# Driver.net
KiCad netlist of a schematic drawn in Altium Designer
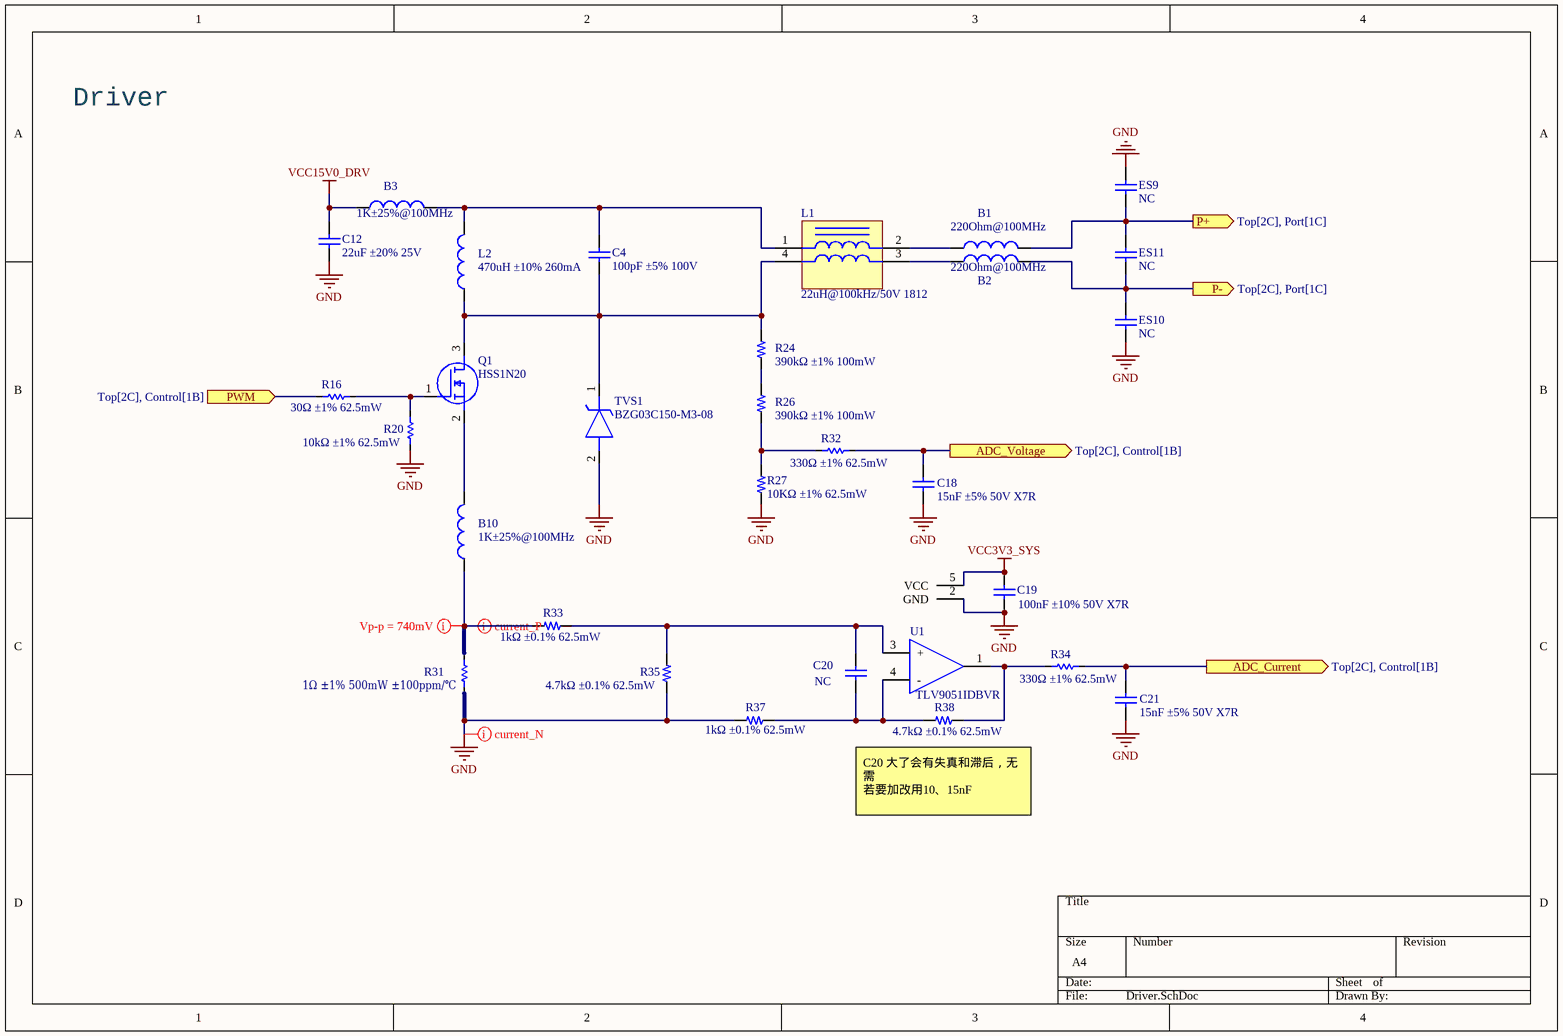
[diagram p0: Driver.SchDoc]

(export (version "E")
  (design (tool "Eeschema 10.0.6"))
  (components
    (comp (ref "B1")
      (value "220Ohm@100MHz")
      (footprint "0402-B")
      (description "BLM15AG221SN1D")
      (fields (field (name "PUBLISHER") "Altium Limited"))
      (libsource (lib "Miscellaneous Devices") (part "Inductor"))
    )
    (comp (ref "B2")
      (value "220Ohm@100MHz")
      (footprint "0402-B")
      (description "BLM15AG221SN1D")
      (fields (field (name "PUBLISHER") "Altium Limited"))
      (libsource (lib "Miscellaneous Devices") (part "Inductor"))
    )
    (comp (ref "B3")
      (value "1K±25%@100MHz")
      (footprint "0805-B")
      (description "BLM21AG102SN1D")
      (fields (field (name "PUBLISHER") "Altium Limited"))
      (libsource (lib "Miscellaneous Devices") (part "Inductor"))
    )
    (comp (ref "B10")
      (value "1K±25%@100MHz")
      (footprint "0805-B")
      (description "BLM21AG102SN1D")
      (fields (field (name "PUBLISHER") "Altium Limited"))
      (libsource (lib "Miscellaneous Devices") (part "Inductor"))
    )
    (comp (ref "C4")
      (value "100pF ±5% 100V")
      (footprint "C0603")
      (description "GCM1885C2A101JA16D")
      (fields (field (name "PUBLISHER") "Altium Limited"))
      (libsource (lib "Miscellaneous Devices") (part "Cap Semi"))
    )
    (comp (ref "C12")
      (value "22uF ±20% 25V")
      (footprint "C0805")
      (description "CL21A226MAQNNNE")
      (fields (field (name "PUBLISHER") "Altium Limited"))
      (libsource (lib "Component") (part "C0805"))
    )
    (comp (ref "C18")
      (value "15nF ±5% 50V X7R")
      (footprint "C0402")
      (description "CC0402KRX7R9BB153")
      (fields (field (name "PUBLISHER") "Altium Limited"))
      (libsource (lib "Component") (part "Cap"))
    )
    (comp (ref "C19")
      (value "100nF ±10% 50V X7R")
      (footprint "C0402")
      (description "CL05B104KO5NNNC")
      (fields (field (name "PUBLISHER") "Altium Limited"))
      (libsource (lib "Component") (part "Cap"))
    )
    (comp (ref "C20")
      (value "NC")
      (footprint "C0402")
      (description "10nF 50V 0402")
      (libsource (lib "电容") (part "100nF_1"))
    )
    (comp (ref "C21")
      (value "15nF ±5% 50V X7R")
      (footprint "C0402")
      (description "CC0402KRX7R9BB153")
      (fields (field (name "PUBLISHER") "Altium Limited"))
      (libsource (lib "Component") (part "Cap"))
    )
    (comp (ref "ES9")
      (value "NC")
      (footprint "C0402")
      (description "Capacitor (Semiconductor SIM Model)")
      (fields (field (name "PUBLISHER") "Altium Limited"))
      (libsource (lib "Miscellaneous Devices") (part "Cap Semi"))
    )
    (comp (ref "ES10")
      (value "NC")
      (footprint "C0402")
      (description "Capacitor (Semiconductor SIM Model)")
      (fields (field (name "PUBLISHER") "Altium Limited"))
      (libsource (lib "Miscellaneous Devices") (part "Cap Semi"))
    )
    (comp (ref "ES11")
      (value "NC")
      (footprint "C0402")
      (description "Capacitor (Semiconductor SIM Model)")
      (fields (field (name "PUBLISHER") "Altium Limited"))
      (libsource (lib "Miscellaneous Devices") (part "Cap Semi"))
    )
    (comp (ref "L1")
      (value "22uH@100kHz/50V 1812")
      (footprint "LINEFILTER")
      (description "APWB4532-220T2")
      (libsource (lib "Atomizer_medical") (part "Inductor_common"))
    )
    (comp (ref "L2")
      (value "470uH ±10% 260mA")
      (footprint "SP0502")
      (description "SDR0603-471KL")
      (fields (field (name "PUBLISHER") "Altium Limited"))
      (libsource (lib "Miscellaneous Devices") (part "Inductor"))
    )
    (comp (ref "Q1")
      (value "HSS1N20")
      (footprint "SamacSys:SOT95P237X122-3N")
      (description "MOSFET (N-Channel)")
      (fields
        (field (name "MANUFACTURER_PART_NUMBER") "FDN86246")
        (field (name "MOUSER PART NUMBER") "512-FDN86246")
      )
      (libsource (lib "*") (part "FDN86246"))
    )
    (comp (ref "R16")
      (value "30Ω ±1% 62.5mW")
      (footprint "R0402")
      (description "RC0402FR-0730RL")
      (fields (field (name "PUBLISHER") "Altium Limited"))
      (libsource (lib "Component") (part "R0402"))
    )
    (comp (ref "R20")
      (value "10kΩ ±1% 62.5mW")
      (footprint "R0402")
      (description "0402WGF1002TCE")
      (fields (field (name "PUBLISHER") "Altium Limited"))
      (libsource (lib "Component") (part "R0402"))
    )
    (comp (ref "R24")
      (value "390kΩ ±1% 100mW")
      (footprint "R0603")
      (description "RC0603FR-07390KL")
      (libsource (lib "Device") (part "R-0603"))
    )
    (comp (ref "R26")
      (value "390kΩ ±1% 100mW")
      (footprint "R0603")
      (description "RC0603FR-07390KL")
      (libsource (lib "Device") (part "R-0603"))
    )
    (comp (ref "R27")
      (value "10KΩ ±1% 62.5mW")
      (footprint "R0402")
      (description "0402WGF1002TCE")
      (libsource (lib "Device") (part "R-0603"))
    )
    (comp (ref "R31")
      (value "1Ω ±1% 500mW ±100ppm/℃")
      (footprint "R1206")
      (description "HP06W2F100KT5E")
      (fields (field (name "PUBLISHER") "Altium Limited"))
      (libsource (lib "Component") (part "R1206"))
    )
    (comp (ref "R32")
      (value "330Ω ±1% 62.5mW")
      (footprint "R0402")
      (description "0402WGF3300TCE")
      (fields (field (name "PUBLISHER") "Altium Limited"))
      (libsource (lib "Component") (part "R0402"))
    )
    (comp (ref "R33")
      (value "1kΩ ±0.1% 62.5mW")
      (footprint "R0402")
      (description "RT0402BRD071KL")
      (libsource (lib "Device") (part "R-0603"))
    )
    (comp (ref "R34")
      (value "330Ω ±1% 62.5mW")
      (footprint "R0402")
      (description "0402WGF3300TCE")
      (fields (field (name "PUBLISHER") "Altium Limited"))
      (libsource (lib "Component") (part "R0402"))
    )
    (comp (ref "R35")
      (value "4.7kΩ ±0.1% 62.5mW")
      (footprint "R0402")
      (description "RT0402BRD074K7L")
      (libsource (lib "Device") (part "R-0603"))
    )
    (comp (ref "R37")
      (value "1kΩ ±0.1% 62.5mW")
      (footprint "R0402")
      (description "RT0402BRD071KL")
      (libsource (lib "Device") (part "R-0603"))
    )
    (comp (ref "R38")
      (value "4.7kΩ ±0.1% 62.5mW")
      (footprint "R0402")
      (description "RT0402BRD074K7L")
      (libsource (lib "Device") (part "R-0603"))
    )
    (comp (ref "TVS1")
      (value "BZG03C150-M3-08")
      (footprint "SamacSys:DIOM5226X230N")
      (description "Zener Diode\r\nBZG03C150-M3-08")
      (fields (field (name "MOUSER PART NUMBER") "78-BZG03C150-M3-08"))
      (libsource (lib "*") (part "BZG03C150-M3-08"))
    )
    (comp (ref "U1")
      (value "TLV9051IDBVR")
      (footprint "SOT23-5")
      (description "TLV9051 适用于成本优化型应用的单路、5.5V、5MHz、15V/μs 压摆率、RRIO 运算放大器")
      (libsource (lib "IC") (part "TLV333IDBVR"))
    )
  )
  (nets
    (net (code "1") (name "/ADC_Current") (class "Default")
      (node (ref "C21") (pin "1") (pinfunction "1_1") (pintype "passive"))
      (node (ref "R34") (pin "2") (pinfunction "2_2") (pintype "passive"))
    )
    (net (code "2") (name "/ADC_Voltage") (class "Default")
      (node (ref "C18") (pin "1") (pinfunction "1_1") (pintype "passive"))
      (node (ref "R32") (pin "2") (pinfunction "2_2") (pintype "passive"))
    )
    (net (code "3") (name "/P+") (class "Default")
      (node (ref "B1") (pin "2") (pinfunction "2_2") (pintype "passive"))
      (node (ref "ES11") (pin "1") (pinfunction "1_1") (pintype "passive"))
      (node (ref "ES9") (pin "2") (pinfunction "2_2") (pintype "passive"))
    )
    (net (code "4") (name "/P-") (class "Default")
      (node (ref "B2") (pin "2") (pinfunction "2_2") (pintype "passive"))
      (node (ref "ES10") (pin "1") (pinfunction "1_1") (pintype "passive"))
      (node (ref "ES11") (pin "2") (pinfunction "2_2") (pintype "passive"))
    )
    (net (code "5") (name "/PWM") (class "Default")
      (node (ref "R16") (pin "1") (pinfunction "1_1") (pintype "passive"))
    )
    (net (code "6") (name "GND") (class "Default")
      (node (ref "C12") (pin "1") (pinfunction "1_1") (pintype "passive"))
      (node (ref "C18") (pin "2") (pinfunction "2_2") (pintype "passive"))
      (node (ref "C19") (pin "1") (pinfunction "1_1") (pintype "passive"))
      (node (ref "C21") (pin "2") (pinfunction "2_2") (pintype "passive"))
      (node (ref "ES10") (pin "2") (pinfunction "2_2") (pintype "passive"))
      (node (ref "ES9") (pin "1") (pinfunction "1_1") (pintype "passive"))
      (node (ref "R20") (pin "1") (pinfunction "1_1") (pintype "passive"))
      (node (ref "R27") (pin "2") (pinfunction "2_2") (pintype "passive"))
      (node (ref "R31") (pin "1") (pinfunction "1_1") (pintype "passive"))
      (node (ref "R35") (pin "1") (pinfunction "1_1") (pintype "passive"))
      (node (ref "R37") (pin "1") (pinfunction "1_1") (pintype "passive"))
      (node (ref "TVS1") (pin "2") (pinfunction "A_2") (pintype "passive"))
      (node (ref "U1") (pin "2") (pinfunction "GND_2") (pintype "passive"))
    )
    (net (code "7") (name "Net-(B1-Pad1)") (class "Default")
      (node (ref "B1") (pin "1") (pinfunction "1_1") (pintype "passive"))
      (node (ref "L1") (pin "2") (pinfunction "2_2") (pintype "passive"))
    )
    (net (code "8") (name "Net-(B2-Pad1)") (class "Default")
      (node (ref "B2") (pin "1") (pinfunction "1_1") (pintype "passive"))
      (node (ref "L1") (pin "3") (pinfunction "3_3") (pintype "passive"))
    )
    (net (code "9") (name "Net-(B3-Pad2)") (class "Default")
      (node (ref "B3") (pin "2") (pinfunction "2_2") (pintype "passive"))
      (node (ref "C4") (pin "1") (pinfunction "1_1") (pintype "passive"))
      (node (ref "L1") (pin "1") (pinfunction "1_1") (pintype "passive"))
      (node (ref "L2") (pin "2") (pinfunction "2_2") (pintype "passive"))
    )
    (net (code "10") (name "Net-(B10-Pad1)") (class "Default")
      (node (ref "B10") (pin "1") (pinfunction "1_1") (pintype "passive"))
      (node (ref "R31") (pin "2") (pinfunction "2_2") (pintype "passive"))
      (node (ref "R33") (pin "1") (pinfunction "1_1") (pintype "passive"))
    )
    (net (code "11") (name "Net-(Q1-D)") (class "Default")
      (node (ref "C4") (pin "2") (pinfunction "2_2") (pintype "passive"))
      (node (ref "L1") (pin "4") (pinfunction "4_4") (pintype "passive"))
      (node (ref "L2") (pin "1") (pinfunction "1_1") (pintype "passive"))
      (node (ref "Q1") (pin "3") (pinfunction "D_3") (pintype "passive"))
      (node (ref "R24") (pin "1") (pinfunction "1_1") (pintype "passive"))
      (node (ref "TVS1") (pin "1") (pinfunction "K_1") (pintype "passive"))
    )
    (net (code "12") (name "Net-(Q1-G)") (class "Default")
      (node (ref "Q1") (pin "1") (pinfunction "G_1") (pintype "passive"))
      (node (ref "R16") (pin "2") (pinfunction "2_2") (pintype "passive"))
      (node (ref "R20") (pin "2") (pinfunction "2_2") (pintype "passive"))
    )
    (net (code "13") (name "Net-(Q1-S)") (class "Default")
      (node (ref "B10") (pin "2") (pinfunction "2_2") (pintype "passive"))
      (node (ref "Q1") (pin "2") (pinfunction "S_2") (pintype "passive"))
    )
    (net (code "14") (name "Net-(R24-Pad2)") (class "Default")
      (node (ref "R24") (pin "2") (pinfunction "2_2") (pintype "passive"))
      (node (ref "R26") (pin "1") (pinfunction "1_1") (pintype "passive"))
    )
    (net (code "15") (name "Net-(R26-Pad2)") (class "Default")
      (node (ref "R26") (pin "2") (pinfunction "2_2") (pintype "passive"))
      (node (ref "R27") (pin "1") (pinfunction "1_1") (pintype "passive"))
      (node (ref "R32") (pin "1") (pinfunction "1_1") (pintype "passive"))
    )
    (net (code "16") (name "Net-(R34-Pad1)") (class "Default")
      (node (ref "R34") (pin "1") (pinfunction "1_1") (pintype "passive"))
      (node (ref "R38") (pin "1") (pinfunction "1_1") (pintype "passive"))
      (node (ref "U1") (pin "1") (pintype "passive"))
    )
    (net (code "17") (name "Net-(U1-+)") (class "Default")
      (node (ref "C20") (pin "2") (pinfunction "2_2") (pintype "passive"))
      (node (ref "R33") (pin "2") (pinfunction "2_2") (pintype "passive"))
      (node (ref "R35") (pin "2") (pinfunction "2_2") (pintype "passive"))
      (node (ref "U1") (pin "3") (pinfunction "+_3") (pintype "passive"))
    )
    (net (code "18") (name "Net-(U1--)") (class "Default")
      (node (ref "C20") (pin "1") (pinfunction "1_1") (pintype "passive"))
      (node (ref "R37") (pin "2") (pinfunction "2_2") (pintype "passive"))
      (node (ref "R38") (pin "2") (pinfunction "2_2") (pintype "passive"))
      (node (ref "U1") (pin "4") (pinfunction "-_4") (pintype "passive"))
    )
    (net (code "19") (name "VCC3V3_SYS") (class "Default")
      (node (ref "C19") (pin "2") (pinfunction "2_2") (pintype "passive"))
      (node (ref "U1") (pin "5") (pinfunction "VCC_5") (pintype "passive"))
    )
    (net (code "20") (name "VCC15V0_DRV") (class "Default")
      (node (ref "B3") (pin "1") (pinfunction "1_1") (pintype "passive"))
      (node (ref "C12") (pin "2") (pinfunction "2_2") (pintype "passive"))
    )
  )
)
